# FPGA_ADC_TOP.net
KiCad netlist of a schematic drawn in Altium Designer
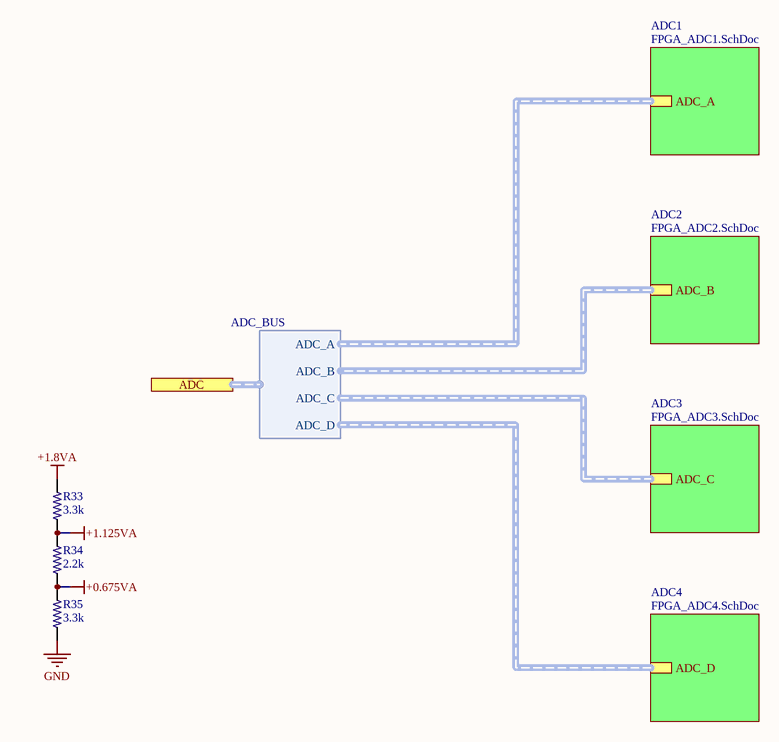
[diagram p0: FPGA_ADC_TOP.SchDoc]

(export (version "E")
  (design (tool "Eeschema 10.0.6"))
  (components
    (comp (ref "R33")
      (value "3.3k")
      (footprint "R0603-HIGH-DENSITY")
      (description "Chip Resistor, 0603, 3.3k ohms, 0.1W")
      (fields (field (name "Comment") "R0603 3.3k 1%"))
      (libsource (lib "Resistors") (part "R0603 3.3k 1%"))
    )
    (comp (ref "R34")
      (value "2.2k")
      (footprint "R0603-HIGH-DENSITY")
      (description "RES SMD 2.2K OHM 1% 1/10W 0603")
      (fields (field (name "Comment") "R0603 2.2K 1%"))
      (libsource (lib "Resistors") (part "R0603 2.2K 1%"))
    )
    (comp (ref "R35")
      (value "3.3k")
      (footprint "R0603-HIGH-DENSITY")
      (description "Chip Resistor, 0603, 3.3k ohms, 0.1W")
      (fields (field (name "Comment") "R0603 3.3k 1%"))
      (libsource (lib "Resistors") (part "R0603 3.3k 1%"))
    )
  )
  (nets
    (net (code "3") (name "+0.675VA") (class "Default")
      (node (ref "R34") (pin "1") (pintype "passive"))
      (node (ref "R35") (pin "2") (pintype "passive"))
    )
    (net (code "4") (name "+1.8VA") (class "Default") (node (ref "R33") (pin "2") (pintype "passive")))
    (net (code "5") (name "+1.125VA") (class "Default")
      (node (ref "R33") (pin "1") (pintype "passive"))
      (node (ref "R34") (pin "2") (pintype "passive"))
    )
    (net (code "11") (name "GND") (class "Default") (node (ref "R35") (pin "1") (pintype "passive")))
  )
)
